# PAGE2_-MCU.net
KiCad netlist of a schematic drawn in Altium Designer
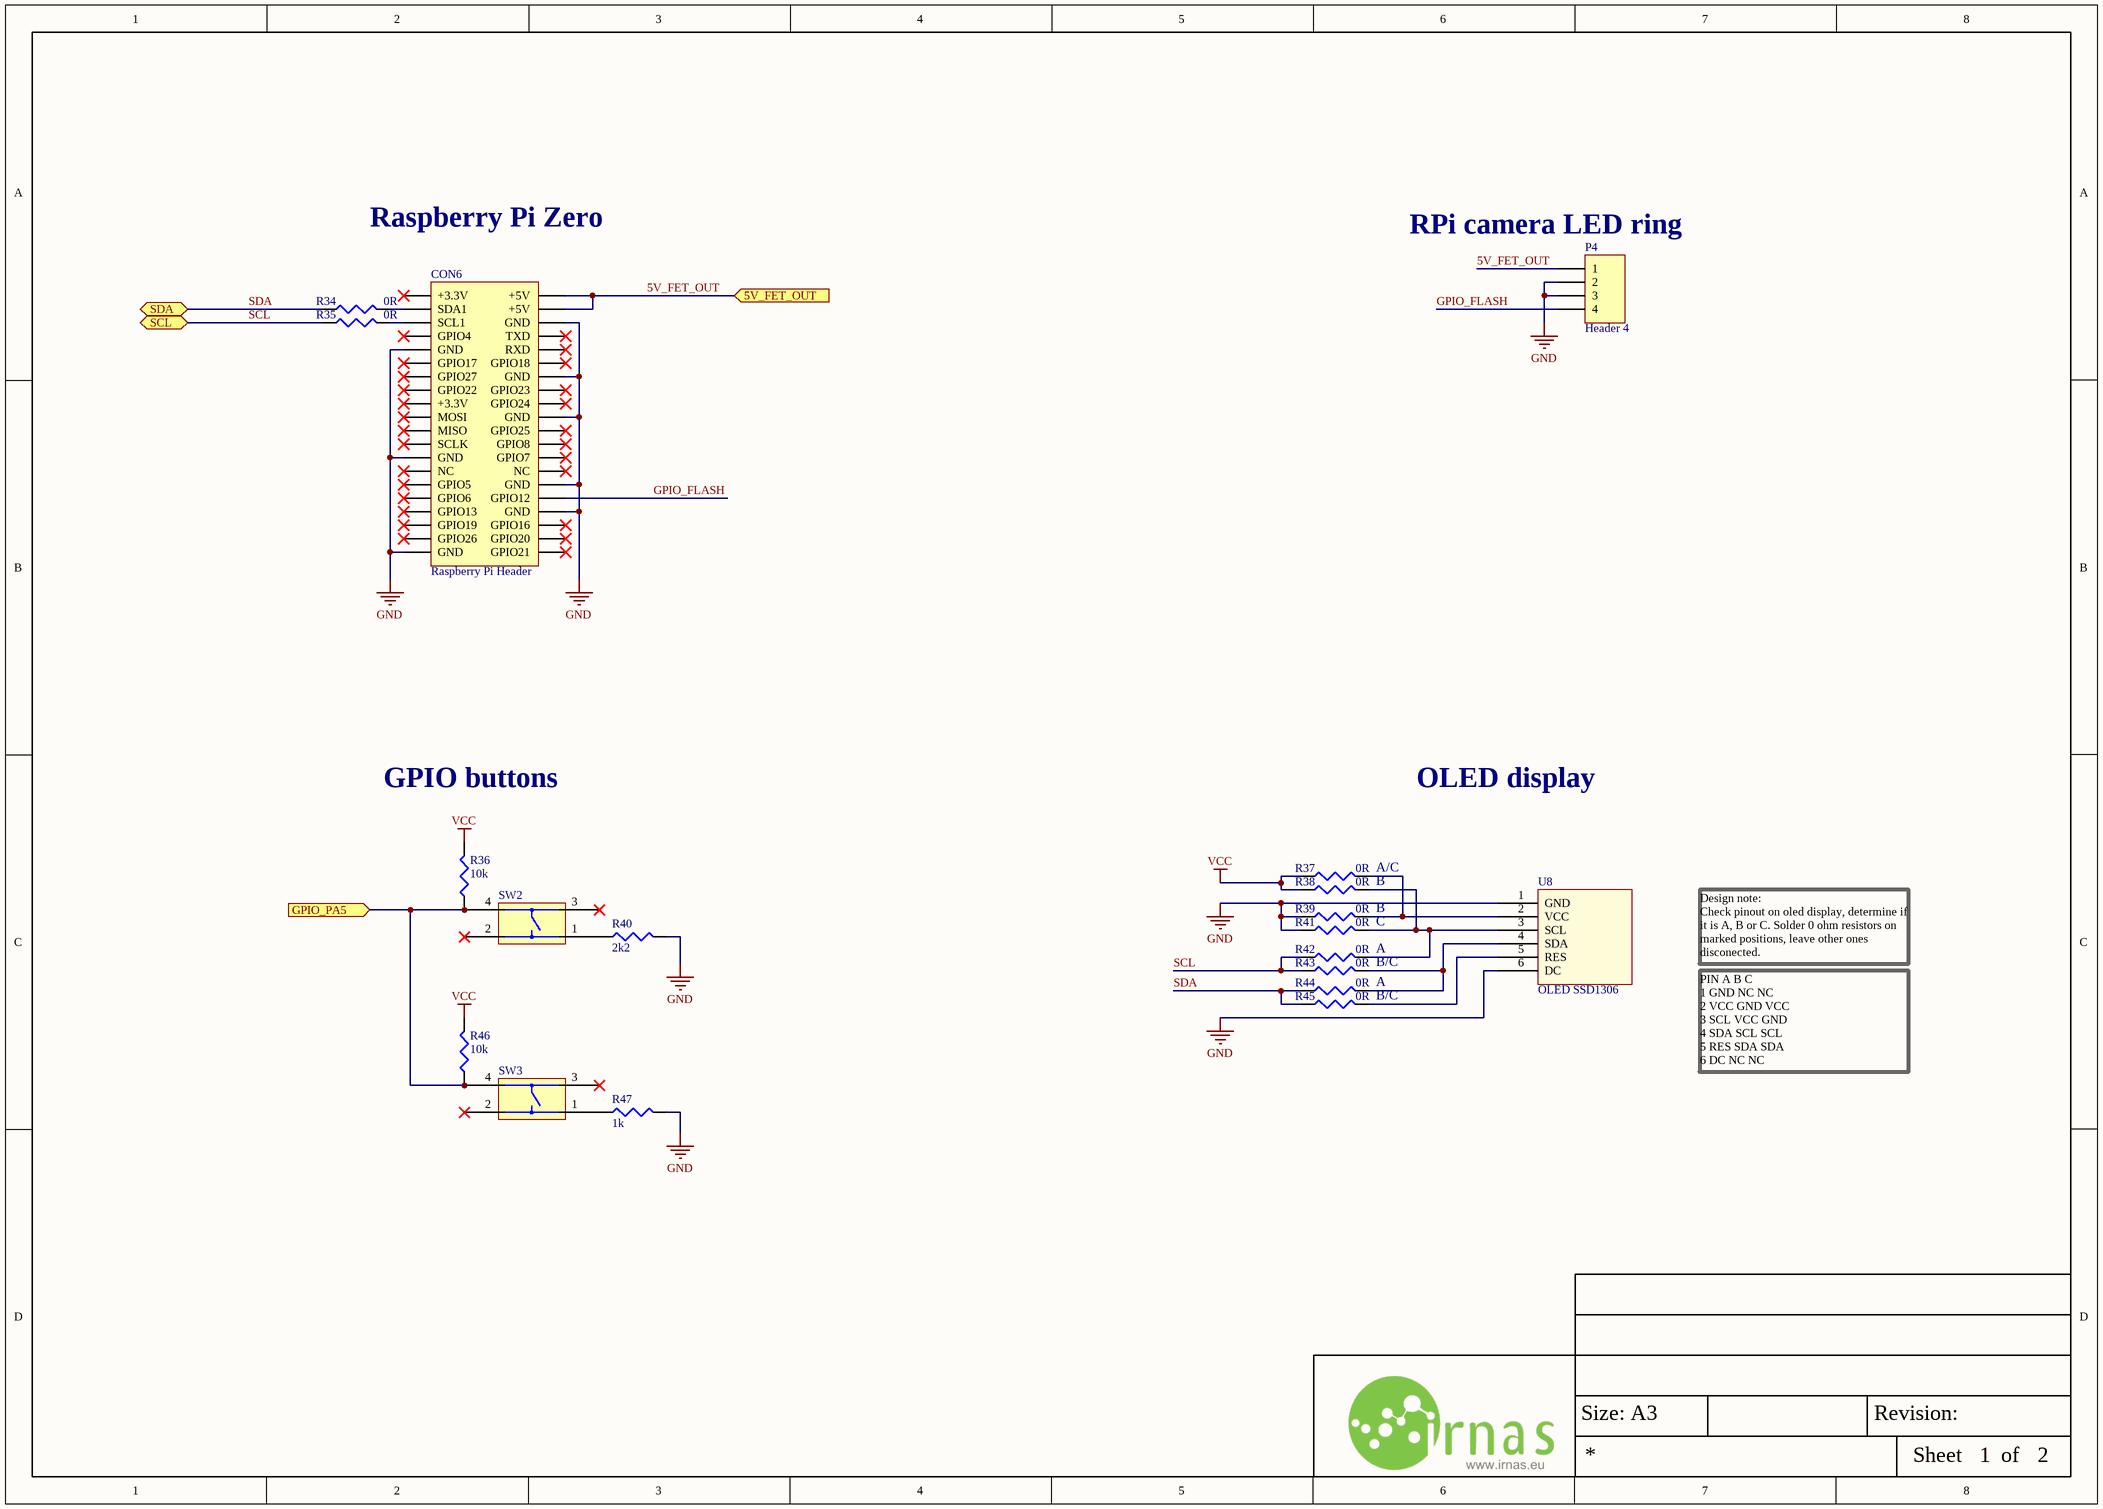
[diagram p0: PAGE2 -MCU.SchDoc]

(export (version "E")
  (design (tool "Eeschema 10.0.6"))
  (components
    (comp (ref "CON6")
      (value "Raspberry Pi Header")
      (footprint "Connectors:HDR2X20")
      (description "Header, 20-Pin, Dual row")
      (fields (field (name "PUBLISHER") "Altium Limited"))
      (libsource (lib "Connectors") (part "Raspberry Pi Header"))
    )
    (comp (ref "P4")
      (value "Header 4")
      (footprint "HDR1X4")
      (description "Header, 4-Pin")
      (fields (field (name "PUBLISHER") "Altium Limited"))
      (libsource (lib "Miscellaneous Connectors") (part "Header 4"))
    )
    (comp (ref "R34")
      (value "0R")
      (footprint "RES0603")
      (description "BOURNS - CR0603-J/-000ELF - RES, THICK FILM, 0R, 5%, 0.1W, 0603")
      (fields
        (field (name "MANUFACTURER") "BOURNS")
        (field (name "MANUFACTURER PART NUMBER") "CR0603-J/-000ELF")
      )
      (libsource (lib "Passive") (part "R - 0R"))
    )
    (comp (ref "R35")
      (value "0R")
      (footprint "RES0603")
      (description "BOURNS - CR0603-J/-000ELF - RES, THICK FILM, 0R, 5%, 0.1W, 0603")
      (fields
        (field (name "MANUFACTURER") "BOURNS")
        (field (name "MANUFACTURER PART NUMBER") "CR0603-J/-000ELF")
      )
      (libsource (lib "Passive") (part "R - 0R"))
    )
    (comp (ref "R36")
      (value "10k")
      (footprint "RES0603")
      (description "MULTICOMP - MCMR06X103 JTL - RES, CERAMIC, 10K, 5%, 0.1W, 0603")
      (fields
        (field (name "MANUFACTURER") "MULTICOMP")
        (field (name "MANUFACTURER PART NUMBER") "MCMR06X103 JTL")
      )
      (libsource (lib "Passive") (part "R - 10k"))
    )
    (comp (ref "R37")
      (value "0R")
      (footprint "RES0603")
      (description "BOURNS - CR0603-J/-000ELF - RES, THICK FILM, 0R, 5%, 0.1W, 0603")
      (fields
        (field (name "MANUFACTURER") "BOURNS")
        (field (name "MANUFACTURER PART NUMBER") "CR0603-J/-000ELF")
      )
      (libsource (lib "Passive") (part "R - 0R"))
    )
    (comp (ref "R38")
      (value "0R")
      (footprint "RES0603")
      (description "BOURNS - CR0603-J/-000ELF - RES, THICK FILM, 0R, 5%, 0.1W, 0603")
      (fields
        (field (name "MANUFACTURER") "BOURNS")
        (field (name "MANUFACTURER PART NUMBER") "CR0603-J/-000ELF")
      )
      (libsource (lib "Passive") (part "R - 0R"))
    )
    (comp (ref "R39")
      (value "0R")
      (footprint "RES0603")
      (description "BOURNS - CR0603-J/-000ELF - RES, THICK FILM, 0R, 5%, 0.1W, 0603")
      (fields
        (field (name "MANUFACTURER") "BOURNS")
        (field (name "MANUFACTURER PART NUMBER") "CR0603-J/-000ELF")
      )
      (libsource (lib "Passive") (part "R - 0R"))
    )
    (comp (ref "R40")
      (value "2k2")
      (footprint "RES0603")
      (description "MULTICOMP - MCMR06X2201FTL - RES, CERAMIC, 2K2, 1%, 0.1W, 0603")
      (fields
        (field (name "MANUFACTURER") "MULTICOMP")
        (field (name "MANUFACTURER PART NUMBER") "MCMR06X2201FTL")
      )
      (libsource (lib "Passive") (part "R - 2k2"))
    )
    (comp (ref "R41")
      (value "0R")
      (footprint "RES0603")
      (description "BOURNS - CR0603-J/-000ELF - RES, THICK FILM, 0R, 5%, 0.1W, 0603")
      (fields
        (field (name "MANUFACTURER") "BOURNS")
        (field (name "MANUFACTURER PART NUMBER") "CR0603-J/-000ELF")
      )
      (libsource (lib "Passive") (part "R - 0R"))
    )
    (comp (ref "R42")
      (value "0R")
      (footprint "RES0603")
      (description "BOURNS - CR0603-J/-000ELF - RES, THICK FILM, 0R, 5%, 0.1W, 0603")
      (fields
        (field (name "MANUFACTURER") "BOURNS")
        (field (name "MANUFACTURER PART NUMBER") "CR0603-J/-000ELF")
      )
      (libsource (lib "Passive") (part "R - 0R"))
    )
    (comp (ref "R43")
      (value "0R")
      (footprint "RES0603")
      (description "BOURNS - CR0603-J/-000ELF - RES, THICK FILM, 0R, 5%, 0.1W, 0603")
      (fields
        (field (name "MANUFACTURER") "BOURNS")
        (field (name "MANUFACTURER PART NUMBER") "CR0603-J/-000ELF")
      )
      (libsource (lib "Passive") (part "R - 0R"))
    )
    (comp (ref "R44")
      (value "0R")
      (footprint "RES0603")
      (description "BOURNS - CR0603-J/-000ELF - RES, THICK FILM, 0R, 5%, 0.1W, 0603")
      (fields
        (field (name "MANUFACTURER") "BOURNS")
        (field (name "MANUFACTURER PART NUMBER") "CR0603-J/-000ELF")
      )
      (libsource (lib "Passive") (part "R - 0R"))
    )
    (comp (ref "R45")
      (value "0R")
      (footprint "RES0603")
      (description "BOURNS - CR0603-J/-000ELF - RES, THICK FILM, 0R, 5%, 0.1W, 0603")
      (fields
        (field (name "MANUFACTURER") "BOURNS")
        (field (name "MANUFACTURER PART NUMBER") "CR0603-J/-000ELF")
      )
      (libsource (lib "Passive") (part "R - 0R"))
    )
    (comp (ref "R46")
      (value "10k")
      (footprint "RES0603")
      (description "MULTICOMP - MCMR06X103 JTL - RES, CERAMIC, 10K, 5%, 0.1W, 0603")
      (fields
        (field (name "MANUFACTURER") "MULTICOMP")
        (field (name "MANUFACTURER PART NUMBER") "MCMR06X103 JTL")
      )
      (libsource (lib "Passive") (part "R - 10k"))
    )
    (comp (ref "R47")
      (value "1k")
      (footprint "RES0603")
      (description "MULTICOMP - MCMR06X102 JTL - RES, CERAMIC, 1K, 5%, 0.1W, 0603")
      (fields
        (field (name "MANUFACTURER") "MULTICOMP")
        (field (name "MANUFACTURER PART NUMBER") "MCMR06X102 JTL")
      )
      (libsource (lib "Passive") (part "R - 1k"))
    )
    (comp (ref "SW2")
      (value "BTN - B3F-1070")
      (footprint "BTN B3F-1070")
      (description "Tactile Switch, B3F Series, Top Actuated, Through Hole, Round Button, 100 gf, 50mA at 24VDC")
      (libsource (lib "Mechanical") (part "BTN - B3F-1070"))
    )
    (comp (ref "SW3")
      (value "BTN - B3F-1070")
      (footprint "BTN B3F-1070")
      (description "Tactile Switch, B3F Series, Top Actuated, Through Hole, Round Button, 100 gf, 50mA at 24VDC")
      (libsource (lib "Mechanical") (part "BTN - B3F-1070"))
    )
    (comp (ref "U8")
      (value "OLED SSD1306")
      (footprint "OLED SSD1306")
      (libsource (lib "oled") (part "OLED SSD1306"))
    )
  )
  (nets
    (net (code "1") (name "/5V_FET_OUT") (class "Default")
      (node (ref "CON6") (pin "2") (pinfunction "+5V_2") (pintype "passive"))
      (node (ref "CON6") (pin "4") (pinfunction "+5V_4") (pintype "passive"))
      (node (ref "P4") (pin "1") (pinfunction "1_1") (pintype "passive"))
    )
    (net (code "2") (name "/GPIO_FLASH") (class "Default")
      (node (ref "CON6") (pin "32") (pinfunction "GPIO12_32") (pintype "passive"))
      (node (ref "P4") (pin "4") (pinfunction "4_4") (pintype "passive"))
    )
    (net (code "3") (name "/GPIO_PA5") (class "Default")
      (node (ref "R36") (pin "1") (pinfunction "1_1") (pintype "passive"))
      (node (ref "R46") (pin "1") (pinfunction "1_1") (pintype "passive"))
      (node (ref "SW2") (pin "4") (pinfunction "4_4") (pintype "passive"))
      (node (ref "SW3") (pin "4") (pinfunction "4_4") (pintype "passive"))
    )
    (net (code "4") (name "/SCL") (class "Default")
      (node (ref "R35") (pin "1") (pinfunction "1_1") (pintype "passive"))
      (node (ref "R42") (pin "1") (pinfunction "1_1") (pintype "passive"))
      (node (ref "R43") (pin "1") (pinfunction "1_1") (pintype "passive"))
    )
    (net (code "5") (name "/SDA") (class "Default")
      (node (ref "R34") (pin "1") (pinfunction "1_1") (pintype "passive"))
      (node (ref "R44") (pin "1") (pinfunction "1_1") (pintype "passive"))
      (node (ref "R45") (pin "1") (pinfunction "1_1") (pintype "passive"))
    )
    (net (code "6") (name "GND") (class "Default")
      (node (ref "CON6") (pin "14") (pinfunction "GND_14") (pintype "passive"))
      (node (ref "CON6") (pin "20") (pinfunction "GND_20") (pintype "passive"))
      (node (ref "CON6") (pin "25") (pinfunction "GND_25") (pintype "passive"))
      (node (ref "CON6") (pin "30") (pinfunction "GND_30") (pintype "passive"))
      (node (ref "CON6") (pin "34") (pinfunction "GND_34") (pintype "passive"))
      (node (ref "CON6") (pin "39") (pinfunction "GND_39") (pintype "passive"))
      (node (ref "CON6") (pin "6") (pinfunction "GND_6") (pintype "passive"))
      (node (ref "CON6") (pin "9") (pinfunction "GND_9") (pintype "passive"))
      (node (ref "P4") (pin "2") (pinfunction "2_2") (pintype "passive"))
      (node (ref "P4") (pin "3") (pinfunction "3_3") (pintype "passive"))
      (node (ref "R39") (pin "1") (pinfunction "1_1") (pintype "passive"))
      (node (ref "R40") (pin "2") (pinfunction "2_2") (pintype "passive"))
      (node (ref "R41") (pin "1") (pinfunction "1_1") (pintype "passive"))
      (node (ref "R47") (pin "2") (pinfunction "2_2") (pintype "passive"))
      (node (ref "U8") (pin "1") (pinfunction "GND_1") (pintype "passive"))
      (node (ref "U8") (pin "6") (pinfunction "DC_6") (pintype "passive"))
    )
    (net (code "7") (name "Net-(CON6-SCL1)") (class "Default")
      (node (ref "CON6") (pin "5") (pinfunction "SCL1_5") (pintype "passive"))
      (node (ref "R35") (pin "2") (pinfunction "2_2") (pintype "passive"))
    )
    (net (code "8") (name "Net-(CON6-SDA1)") (class "Default")
      (node (ref "CON6") (pin "3") (pinfunction "SDA1_3") (pintype "passive"))
      (node (ref "R34") (pin "2") (pinfunction "2_2") (pintype "passive"))
    )
    (net (code "9") (name "Net-(R40-Pad1)") (class "Default")
      (node (ref "R40") (pin "1") (pinfunction "1_1") (pintype "passive"))
      (node (ref "SW2") (pin "1") (pinfunction "1_1") (pintype "passive"))
    )
    (net (code "10") (name "Net-(R47-Pad1)") (class "Default")
      (node (ref "R47") (pin "1") (pinfunction "1_1") (pintype "passive"))
      (node (ref "SW3") (pin "1") (pinfunction "1_1") (pintype "passive"))
    )
    (net (code "11") (name "Net-(U8-RES)") (class "Default")
      (node (ref "R45") (pin "2") (pinfunction "2_2") (pintype "passive"))
      (node (ref "U8") (pin "5") (pinfunction "RES_5") (pintype "passive"))
    )
    (net (code "12") (name "Net-(U8-SCL)") (class "Default")
      (node (ref "R38") (pin "2") (pinfunction "2_2") (pintype "passive"))
      (node (ref "R41") (pin "2") (pinfunction "2_2") (pintype "passive"))
      (node (ref "R42") (pin "2") (pinfunction "2_2") (pintype "passive"))
      (node (ref "U8") (pin "3") (pinfunction "SCL_3") (pintype "passive"))
    )
    (net (code "13") (name "Net-(U8-SDA)") (class "Default")
      (node (ref "R43") (pin "2") (pinfunction "2_2") (pintype "passive"))
      (node (ref "R44") (pin "2") (pinfunction "2_2") (pintype "passive"))
      (node (ref "U8") (pin "4") (pinfunction "SDA_4") (pintype "passive"))
    )
    (net (code "14") (name "Net-(U8-VCC)") (class "Default")
      (node (ref "R37") (pin "2") (pinfunction "2_2") (pintype "passive"))
      (node (ref "R39") (pin "2") (pinfunction "2_2") (pintype "passive"))
      (node (ref "U8") (pin "2") (pinfunction "VCC_2") (pintype "passive"))
    )
    (net (code "15") (name "VCC") (class "Default")
      (node (ref "R36") (pin "2") (pinfunction "2_2") (pintype "passive"))
      (node (ref "R37") (pin "1") (pinfunction "1_1") (pintype "passive"))
      (node (ref "R38") (pin "1") (pinfunction "1_1") (pintype "passive"))
      (node (ref "R46") (pin "2") (pinfunction "2_2") (pintype "passive"))
    )
    (net (code "16") (name "unconnected-(CON6-+3.3V-Pad1)") (class "Default")
      (node (ref "CON6") (pin "1") (pinfunction "+3.3V_1") (pintype "passive+no_connect"))
    )
    (net (code "17") (name "unconnected-(CON6-+3.3V-Pad17)") (class "Default")
      (node (ref "CON6") (pin "17") (pinfunction "+3.3V_17") (pintype "passive+no_connect"))
    )
    (net (code "18") (name "unconnected-(CON6-GPIO4-Pad7)") (class "Default")
      (node (ref "CON6") (pin "7") (pinfunction "GPIO4_7") (pintype "passive+no_connect"))
    )
    (net (code "19") (name "unconnected-(CON6-GPIO5-Pad29)") (class "Default")
      (node (ref "CON6") (pin "29") (pinfunction "GPIO5_29") (pintype "passive+no_connect"))
    )
    (net (code "20") (name "unconnected-(CON6-GPIO6-Pad31)") (class "Default")
      (node (ref "CON6") (pin "31") (pinfunction "GPIO6_31") (pintype "passive+no_connect"))
    )
    (net (code "21") (name "unconnected-(CON6-GPIO7-Pad26)") (class "Default")
      (node (ref "CON6") (pin "26") (pinfunction "GPIO7_26") (pintype "passive+no_connect"))
    )
    (net (code "22") (name "unconnected-(CON6-GPIO8-Pad24)") (class "Default")
      (node (ref "CON6") (pin "24") (pinfunction "GPIO8_24") (pintype "passive+no_connect"))
    )
    (net (code "23") (name "unconnected-(CON6-GPIO13-Pad33)") (class "Default")
      (node (ref "CON6") (pin "33") (pinfunction "GPIO13_33") (pintype "passive+no_connect"))
    )
    (net (code "24") (name "unconnected-(CON6-GPIO16-Pad36)") (class "Default")
      (node (ref "CON6") (pin "36") (pinfunction "GPIO16_36") (pintype "passive+no_connect"))
    )
    (net (code "25") (name "unconnected-(CON6-GPIO17-Pad11)") (class "Default")
      (node (ref "CON6") (pin "11") (pinfunction "GPIO17_11") (pintype "passive+no_connect"))
    )
    (net (code "26") (name "unconnected-(CON6-GPIO18-Pad12)") (class "Default")
      (node (ref "CON6") (pin "12") (pinfunction "GPIO18_12") (pintype "passive+no_connect"))
    )
    (net (code "27") (name "unconnected-(CON6-GPIO19-Pad35)") (class "Default")
      (node (ref "CON6") (pin "35") (pinfunction "GPIO19_35") (pintype "passive+no_connect"))
    )
    (net (code "28") (name "unconnected-(CON6-GPIO20-Pad38)") (class "Default")
      (node (ref "CON6") (pin "38") (pinfunction "GPIO20_38") (pintype "passive+no_connect"))
    )
    (net (code "29") (name "unconnected-(CON6-GPIO21-Pad40)") (class "Default")
      (node (ref "CON6") (pin "40") (pinfunction "GPIO21_40") (pintype "passive+no_connect"))
    )
    (net (code "30") (name "unconnected-(CON6-GPIO22-Pad15)") (class "Default")
      (node (ref "CON6") (pin "15") (pinfunction "GPIO22_15") (pintype "passive+no_connect"))
    )
    (net (code "31") (name "unconnected-(CON6-GPIO23-Pad16)") (class "Default")
      (node (ref "CON6") (pin "16") (pinfunction "GPIO23_16") (pintype "passive+no_connect"))
    )
    (net (code "32") (name "unconnected-(CON6-GPIO24-Pad18)") (class "Default")
      (node (ref "CON6") (pin "18") (pinfunction "GPIO24_18") (pintype "passive+no_connect"))
    )
    (net (code "33") (name "unconnected-(CON6-GPIO25-Pad22)") (class "Default")
      (node (ref "CON6") (pin "22") (pinfunction "GPIO25_22") (pintype "passive+no_connect"))
    )
    (net (code "34") (name "unconnected-(CON6-GPIO26-Pad37)") (class "Default")
      (node (ref "CON6") (pin "37") (pinfunction "GPIO26_37") (pintype "passive+no_connect"))
    )
    (net (code "35") (name "unconnected-(CON6-GPIO27-Pad13)") (class "Default")
      (node (ref "CON6") (pin "13") (pinfunction "GPIO27_13") (pintype "passive+no_connect"))
    )
    (net (code "36") (name "unconnected-(CON6-MISO-Pad21)") (class "Default")
      (node (ref "CON6") (pin "21") (pinfunction "MISO_21") (pintype "passive+no_connect"))
    )
    (net (code "37") (name "unconnected-(CON6-MOSI-Pad19)") (class "Default")
      (node (ref "CON6") (pin "19") (pinfunction "MOSI_19") (pintype "passive+no_connect"))
    )
    (net (code "38") (name "unconnected-(CON6-NC-Pad27)") (class "Default")
      (node (ref "CON6") (pin "27") (pinfunction "NC_27") (pintype "passive+no_connect"))
    )
    (net (code "39") (name "unconnected-(CON6-NC-Pad28)") (class "Default")
      (node (ref "CON6") (pin "28") (pinfunction "NC_28") (pintype "passive+no_connect"))
    )
    (net (code "40") (name "unconnected-(CON6-RXD-Pad10)") (class "Default")
      (node (ref "CON6") (pin "10") (pinfunction "RXD_10") (pintype "passive+no_connect"))
    )
    (net (code "41") (name "unconnected-(CON6-SCLK-Pad23)") (class "Default")
      (node (ref "CON6") (pin "23") (pinfunction "SCLK_23") (pintype "passive+no_connect"))
    )
    (net (code "42") (name "unconnected-(CON6-TXD-Pad8)") (class "Default")
      (node (ref "CON6") (pin "8") (pinfunction "TXD_8") (pintype "passive+no_connect"))
    )
    (net (code "43") (name "unconnected-(SW2-Pad2)") (class "Default")
      (node (ref "SW2") (pin "2") (pinfunction "2_2") (pintype "passive+no_connect"))
    )
    (net (code "44") (name "unconnected-(SW2-Pad3)") (class "Default")
      (node (ref "SW2") (pin "3") (pinfunction "3_3") (pintype "passive+no_connect"))
    )
    (net (code "45") (name "unconnected-(SW3-Pad2)") (class "Default")
      (node (ref "SW3") (pin "2") (pinfunction "2_2") (pintype "passive+no_connect"))
    )
    (net (code "46") (name "unconnected-(SW3-Pad3)") (class "Default")
      (node (ref "SW3") (pin "3") (pinfunction "3_3") (pintype "passive+no_connect"))
    )
  )
)
